# Sheet1.net
KiCad netlist of a schematic drawn in Altium Designer
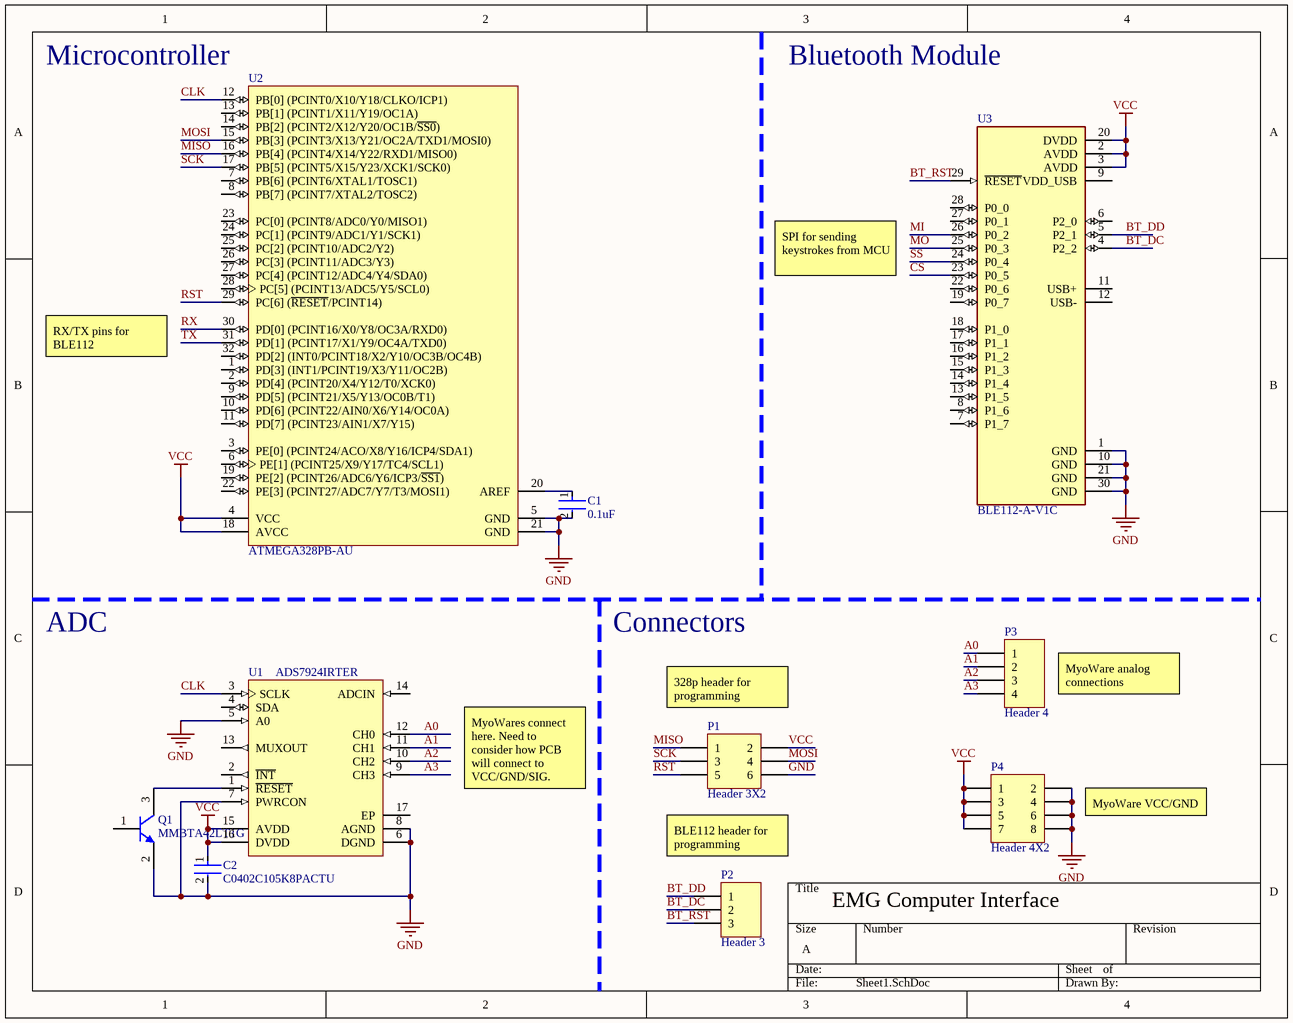
[diagram p0: Sheet1.SchDoc]

(export (version "E")
  (design (tool "Eeschema 10.0.6"))
  (components
    (comp (ref "C1")
      (value "0.1uF")
      (footprint "FP-GRM033-0_03-IPC_C")
      (description "Chip Multilayer Ceramic Capacitors for General Purpose, 0201, 0.10uF, X5R, 15%, 10%, 10V")
      (fields (field (name "TOLERANCE") "10%") (field (name "VOLTAGE") "10V"))
      (libsource (lib "Altium Content Vault") (part "b4654b650e69147ec39a6b967a45e02"))
    )
    (comp (ref "C2")
      (value "C0402C105K8PACTU")
      (footprint "FP-C0402C105K8PACTU-MFG")
      (description "CAP CER 1UF 10V X5R 0402")
      (fields (field (name "VOLTAGE") "10V") (field (name "TOLERANCE") "10%"))
      (libsource (lib "Altium Content Vault") (part "11868f565c42a9108669ba33697ecf6"))
    )
    (comp (ref "P1")
      (value "Header 3X2")
      (footprint "HDR2X3")
      (description "Header, 3-Pin, Dual row")
      (fields (field (name "PUBLISHER") "Altium Limited"))
      (libsource (lib "Miscellaneous Connectors") (part "Header 3X2"))
    )
    (comp (ref "P2")
      (value "Header 3")
      (footprint "HDR1X3")
      (description "Header, 3-Pin")
      (fields (field (name "PUBLISHER") "Altium Limited"))
      (libsource (lib "Miscellaneous Connectors") (part "Header 3"))
    )
    (comp (ref "P3")
      (value "Header 4")
      (footprint "HDR1X4")
      (description "Header, 4-Pin")
      (fields (field (name "PUBLISHER") "Altium Limited"))
      (libsource (lib "Miscellaneous Connectors") (part "Header 4"))
    )
    (comp (ref "P4")
      (value "Header 4X2")
      (footprint "HDR2X4")
      (description "Header, 4-Pin, Dual row")
      (fields (field (name "PUBLISHER") "Altium Limited"))
      (libsource (lib "Miscellaneous Connectors") (part "Header 4X2"))
    )
    (comp (ref "Q1")
      (value "MMBTA42LT1G")
      (footprint "ONSC-SOT-23-3-318-08_V")
      (description "High Voltage Transistor, NPN Silicon, 3-Pin SOT-23, Pb-Free, Tape and Reel")
      (fields (field (name "MANUFACTURER") "On Semiconductor"))
      (libsource (lib "Altium Content Vault") (part "ONSC-NPN-B1E2C3-3"))
    )
    (comp (ref "U1")
      (value "ADS7924IRTER")
      (footprint "TI-RTE16-1700X1700TP_V")
      (fields (field (name "MANUFACTURER") "Texas Instruments"))
      (libsource (lib "Altium Content Vault") (part "TI-ADS7924RTE16-1700X1700TP"))
    )
    (comp (ref "U2")
      (value "ATMEGA328PB-AU")
      (footprint "ATML-32A_L")
      (fields (field (name "MANUFACTURER") "Microchip"))
      (libsource (lib "Altium Content Vault") (part "ATML-ATMEGA328PB-32A"))
    )
    (comp (ref "U3")
      (value "BLE112-A-V1C")
      (footprint "BLUEGIGA_BLE112-A")
      (description "Low Energy Bluetooth Module")
      (libsource (lib "BLE112-A-V1C") (part "BLE112-A-V1C"))
    )
  )
  (nets
    (net (code "1") (name "/A0") (class "Default")
      (node (ref "P3") (pin "1") (pinfunction "1_1") (pintype "passive"))
      (node (ref "U1") (pin "12") (pinfunction "CH0_12") (pintype "input"))
    )
    (net (code "2") (name "/A1") (class "Default")
      (node (ref "P3") (pin "2") (pinfunction "2_2") (pintype "passive"))
      (node (ref "U1") (pin "11") (pinfunction "CH1_11") (pintype "input"))
    )
    (net (code "3") (name "/A2") (class "Default")
      (node (ref "P3") (pin "3") (pinfunction "3_3") (pintype "passive"))
      (node (ref "U1") (pin "10") (pinfunction "CH2_10") (pintype "input"))
    )
    (net (code "4") (name "/A3") (class "Default")
      (node (ref "P3") (pin "4") (pinfunction "4_4") (pintype "passive"))
      (node (ref "U1") (pin "9") (pinfunction "CH3_9") (pintype "input"))
    )
    (net (code "5") (name "/BT_DC") (class "Default")
      (node (ref "P2") (pin "2") (pinfunction "2_2") (pintype "passive"))
      (node (ref "U3") (pin "4") (pinfunction "P2_2_4") (pintype "bidirectional"))
    )
    (net (code "6") (name "/BT_DD") (class "Default")
      (node (ref "P2") (pin "1") (pinfunction "1_1") (pintype "passive"))
      (node (ref "U3") (pin "5") (pinfunction "P2_1_5") (pintype "bidirectional"))
    )
    (net (code "7") (name "/BT_RST") (class "Default")
      (node (ref "P2") (pin "3") (pinfunction "3_3") (pintype "passive"))
      (node (ref "U3") (pin "29") (pinfunction "~{RESET}_29") (pintype "input"))
    )
    (net (code "8") (name "/CLK") (class "Default")
      (node (ref "U1") (pin "3") (pinfunction "SCLK_3") (pintype "input"))
      (node (ref "U2") (pin "12") (pinfunction "PB[0]_(PCINT0/X10/Y18/CLKO/ICP1)_12") (pintype "bidirectional"))
    )
    (net (code "9") (name "/CS") (class "Default")
      (node (ref "U3") (pin "23") (pinfunction "P0_5_23") (pintype "bidirectional"))
    )
    (net (code "10") (name "/MI") (class "Default")
      (node (ref "U3") (pin "26") (pinfunction "P0_2_26") (pintype "bidirectional"))
    )
    (net (code "11") (name "/MISO") (class "Default")
      (node (ref "P1") (pin "1") (pinfunction "1_1") (pintype "passive"))
      (node (ref "U2") (pin "16") (pinfunction "PB[4]_(PCINT4/X14/Y22/RXD1/MISO0)_16") (pintype "bidirectional"))
    )
    (net (code "12") (name "/MO") (class "Default")
      (node (ref "U3") (pin "25") (pinfunction "P0_3_25") (pintype "bidirectional"))
    )
    (net (code "13") (name "/MOSI") (class "Default")
      (node (ref "P1") (pin "4") (pinfunction "4_4") (pintype "passive"))
      (node (ref "U2") (pin "15") (pinfunction "PB[3]_(PCINT3/X13/Y21/OC2A/TXD1/MOSI0)_15") (pintype "bidirectional"))
    )
    (net (code "14") (name "/RST") (class "Default")
      (node (ref "P1") (pin "5") (pinfunction "5_5") (pintype "passive"))
      (node (ref "U2") (pin "29") (pinfunction "PC[6]_(~{RESET}/PCINT14)_29") (pintype "bidirectional"))
    )
    (net (code "15") (name "/RX") (class "Default")
      (node (ref "U2") (pin "30") (pinfunction "PD[0]_(PCINT16/X0/Y8/OC3A/RXD0)_30") (pintype "bidirectional"))
    )
    (net (code "16") (name "/SCK") (class "Default")
      (node (ref "P1") (pin "3") (pinfunction "3_3") (pintype "passive"))
      (node (ref "U2") (pin "17") (pinfunction "PB[5]_(PCINT5/X15/Y23/XCK1/SCK0)_17") (pintype "bidirectional"))
    )
    (net (code "17") (name "/SS") (class "Default")
      (node (ref "U3") (pin "24") (pinfunction "P0_4_24") (pintype "bidirectional"))
    )
    (net (code "18") (name "/TX") (class "Default")
      (node (ref "U2") (pin "31") (pinfunction "PD[1]_(PCINT17/X1/Y9/OC4A/TXD0)_31") (pintype "bidirectional"))
    )
    (net (code "19") (name "GND") (class "Default")
      (node (ref "C1") (pin "2") (pinfunction "2_2") (pintype "passive"))
      (node (ref "C2") (pin "2") (pinfunction "2_2") (pintype "passive"))
      (node (ref "P1") (pin "6") (pinfunction "6_6") (pintype "passive"))
      (node (ref "P4") (pin "2") (pinfunction "2_2") (pintype "passive"))
      (node (ref "P4") (pin "4") (pinfunction "4_4") (pintype "passive"))
      (node (ref "P4") (pin "6") (pinfunction "6_6") (pintype "passive"))
      (node (ref "P4") (pin "8") (pinfunction "8_8") (pintype "passive"))
      (node (ref "Q1") (pin "2") (pinfunction "E_2") (pintype "passive"))
      (node (ref "U1") (pin "5") (pinfunction "A0_5") (pintype "input"))
      (node (ref "U1") (pin "6") (pinfunction "DGND_6") (pintype "power_in"))
      (node (ref "U1") (pin "7") (pinfunction "PWRCON_7") (pintype "input"))
      (node (ref "U1") (pin "8") (pinfunction "AGND_8") (pintype "power_in"))
      (node (ref "U2") (pin "21") (pinfunction "GND_21") (pintype "power_in"))
      (node (ref "U2") (pin "5") (pinfunction "GND_5") (pintype "power_in"))
      (node (ref "U3") (pin "1") (pinfunction "GND_1") (pintype "power_in"))
      (node (ref "U3") (pin "10") (pinfunction "GND_10") (pintype "power_in"))
      (node (ref "U3") (pin "21") (pinfunction "GND_21") (pintype "power_in"))
      (node (ref "U3") (pin "30") (pinfunction "GND_30") (pintype "power_in"))
    )
    (net (code "20") (name "Net-(Q1-C)") (class "Default")
      (node (ref "Q1") (pin "3") (pinfunction "C_3") (pintype "passive"))
      (node (ref "U1") (pin "1") (pinfunction "~{RESET}_1") (pintype "input"))
    )
    (net (code "21") (name "Net-(U2-AREF)") (class "Default")
      (node (ref "C1") (pin "1") (pinfunction "1_1") (pintype "passive"))
      (node (ref "U2") (pin "20") (pinfunction "AREF_20") (pintype "passive"))
    )
    (net (code "22") (name "VCC") (class "Default")
      (node (ref "C2") (pin "1") (pinfunction "1_1") (pintype "passive"))
      (node (ref "P1") (pin "2") (pinfunction "2_2") (pintype "passive"))
      (node (ref "P4") (pin "1") (pinfunction "1_1") (pintype "passive"))
      (node (ref "P4") (pin "3") (pinfunction "3_3") (pintype "passive"))
      (node (ref "P4") (pin "5") (pinfunction "5_5") (pintype "passive"))
      (node (ref "P4") (pin "7") (pinfunction "7_7") (pintype "passive"))
      (node (ref "U1") (pin "15") (pinfunction "AVDD_15") (pintype "power_in"))
      (node (ref "U1") (pin "16") (pinfunction "DVDD_16") (pintype "power_in"))
      (node (ref "U2") (pin "18") (pinfunction "AVCC_18") (pintype "power_in"))
      (node (ref "U2") (pin "4") (pinfunction "VCC_4") (pintype "power_in"))
      (node (ref "U3") (pin "2") (pinfunction "AVDD_2") (pintype "power_in"))
      (node (ref "U3") (pin "20") (pinfunction "DVDD_20") (pintype "power_in"))
      (node (ref "U3") (pin "3") (pinfunction "AVDD_3") (pintype "power_in"))
    )
    (net (code "23") (name "unconnected-(Q1-B-Pad1)") (class "Default")
      (node (ref "Q1") (pin "1") (pinfunction "B_1") (pintype "passive"))
    )
    (net (code "24") (name "unconnected-(U1-ADCIN-Pad14)") (class "Default")
      (node (ref "U1") (pin "14") (pinfunction "ADCIN_14") (pintype "input"))
    )
    (net (code "25") (name "unconnected-(U1-EP-Pad17)") (class "Default")
      (node (ref "U1") (pin "17") (pinfunction "EP_17") (pintype "power_in"))
    )
    (net (code "26") (name "unconnected-(U1-MUXOUT-Pad13)") (class "Default")
      (node (ref "U1") (pin "13") (pinfunction "MUXOUT_13") (pintype "output"))
    )
    (net (code "27") (name "unconnected-(U1-SDA-Pad4)") (class "Default")
      (node (ref "U1") (pin "4") (pinfunction "SDA_4") (pintype "bidirectional"))
    )
    (net (code "28") (name "unconnected-(U1-~{INT}-Pad2)") (class "Default")
      (node (ref "U1") (pin "2") (pinfunction "~{INT}_2") (pintype "output"))
    )
    (net (code "29") (name "unconnected-(U2-PB[1]_(PCINT1{slash}X11{slash}Y19{slash}OC1A)-Pad13)") (class "Default")
      (node (ref "U2") (pin "13") (pinfunction "PB[1]_(PCINT1/X11/Y19/OC1A)_13") (pintype "bidirectional"))
    )
    (net (code "30") (name "unconnected-(U2-PB[2]_(PCINT2{slash}X12{slash}Y20{slash}OC1B{slash}~{SS0})-Pad14)") (class "Default")
      (node (ref "U2") (pin "14") (pinfunction "PB[2]_(PCINT2/X12/Y20/OC1B/~{SS0})_14") (pintype "bidirectional"))
    )
    (net (code "31") (name "unconnected-(U2-PB[6]_(PCINT6{slash}XTAL1{slash}TOSC1)-Pad7)") (class "Default")
      (node (ref "U2") (pin "7") (pinfunction "PB[6]_(PCINT6/XTAL1/TOSC1)_7") (pintype "bidirectional"))
    )
    (net (code "32") (name "unconnected-(U2-PB[7]_(PCINT7{slash}XTAL2{slash}TOSC2)-Pad8)") (class "Default")
      (node (ref "U2") (pin "8") (pinfunction "PB[7]_(PCINT7/XTAL2/TOSC2)_8") (pintype "bidirectional"))
    )
    (net (code "33") (name "unconnected-(U2-PC[0]_(PCINT8{slash}ADC0{slash}Y0{slash}MISO1)-Pad23)") (class "Default")
      (node (ref "U2") (pin "23") (pinfunction "PC[0]_(PCINT8/ADC0/Y0/MISO1)_23") (pintype "bidirectional"))
    )
    (net (code "34") (name "unconnected-(U2-PC[1]_(PCINT9{slash}ADC1{slash}Y1{slash}SCK1)-Pad24)") (class "Default")
      (node (ref "U2") (pin "24") (pinfunction "PC[1]_(PCINT9/ADC1/Y1/SCK1)_24") (pintype "bidirectional"))
    )
    (net (code "35") (name "unconnected-(U2-PC[2]_(PCINT10{slash}ADC2{slash}Y2)-Pad25)") (class "Default")
      (node (ref "U2") (pin "25") (pinfunction "PC[2]_(PCINT10/ADC2/Y2)_25") (pintype "bidirectional"))
    )
    (net (code "36") (name "unconnected-(U2-PC[3]_(PCINT11{slash}ADC3{slash}Y3)-Pad26)") (class "Default")
      (node (ref "U2") (pin "26") (pinfunction "PC[3]_(PCINT11/ADC3/Y3)_26") (pintype "bidirectional"))
    )
    (net (code "37") (name "unconnected-(U2-PC[4]_(PCINT12{slash}ADC4{slash}Y4{slash}SDA0)-Pad27)") (class "Default")
      (node (ref "U2") (pin "27") (pinfunction "PC[4]_(PCINT12/ADC4/Y4/SDA0)_27") (pintype "bidirectional"))
    )
    (net (code "38") (name "unconnected-(U2-PC[5]_(PCINT13{slash}ADC5{slash}Y5{slash}SCL0)-Pad28)") (class "Default")
      (node (ref "U2") (pin "28") (pinfunction "PC[5]_(PCINT13/ADC5/Y5/SCL0)_28") (pintype "bidirectional"))
    )
    (net (code "39") (name "unconnected-(U2-PD[2]_(INT0{slash}PCINT18{slash}X2{slash}Y10{slash}OC3B{slash}OC4B)-Pad32)") (class "Default")
      (node (ref "U2") (pin "32") (pinfunction "PD[2]_(INT0/PCINT18/X2/Y10/OC3B/OC4B)_32") (pintype "bidirectional"))
    )
    (net (code "40") (name "unconnected-(U2-PD[3]_(INT1{slash}PCINT19{slash}X3{slash}Y11{slash}OC2B)-Pad1)") (class "Default")
      (node (ref "U2") (pin "1") (pinfunction "PD[3]_(INT1/PCINT19/X3/Y11/OC2B)_1") (pintype "bidirectional"))
    )
    (net (code "41") (name "unconnected-(U2-PD[4]_(PCINT20{slash}X4{slash}Y12{slash}T0{slash}XCK0)-Pad2)") (class "Default")
      (node (ref "U2") (pin "2") (pinfunction "PD[4]_(PCINT20/X4/Y12/T0/XCK0)_2") (pintype "bidirectional"))
    )
    (net (code "42") (name "unconnected-(U2-PD[5]_(PCINT21{slash}X5{slash}Y13{slash}OC0B{slash}T1)-Pad9)") (class "Default")
      (node (ref "U2") (pin "9") (pinfunction "PD[5]_(PCINT21/X5/Y13/OC0B/T1)_9") (pintype "bidirectional"))
    )
    (net (code "43") (name "unconnected-(U2-PD[6]_(PCINT22{slash}AIN0{slash}X6{slash}Y14{slash}OC0A)-Pad10)") (class "Default")
      (node (ref "U2") (pin "10") (pinfunction "PD[6]_(PCINT22/AIN0/X6/Y14/OC0A)_10") (pintype "bidirectional"))
    )
    (net (code "44") (name "unconnected-(U2-PD[7]_(PCINT23{slash}AIN1{slash}X7{slash}Y15)-Pad11)") (class "Default")
      (node (ref "U2") (pin "11") (pinfunction "PD[7]_(PCINT23/AIN1/X7/Y15)_11") (pintype "bidirectional"))
    )
    (net (code "45") (name "unconnected-(U2-PE[0]_(PCINT24{slash}ACO{slash}X8{slash}Y16{slash}ICP4{slash}SDA1)-Pad3)") (class "Default")
      (node (ref "U2") (pin "3") (pinfunction "PE[0]_(PCINT24/ACO/X8/Y16/ICP4/SDA1)_3") (pintype "bidirectional"))
    )
    (net (code "46") (name "unconnected-(U2-PE[1]_(PCINT25{slash}X9{slash}Y17{slash}TC4{slash}SCL1)-Pad6)") (class "Default")
      (node (ref "U2") (pin "6") (pinfunction "PE[1]_(PCINT25/X9/Y17/TC4/SCL1)_6") (pintype "bidirectional"))
    )
    (net (code "47") (name "unconnected-(U2-PE[2]_(PCINT26{slash}ADC6{slash}Y6{slash}ICP3{slash}~{SS1})-Pad19)") (class "Default")
      (node (ref "U2") (pin "19") (pinfunction "PE[2]_(PCINT26/ADC6/Y6/ICP3/~{SS1})_19") (pintype "bidirectional"))
    )
    (net (code "48") (name "unconnected-(U2-PE[3]_(PCINT27{slash}ADC7{slash}Y7{slash}T3{slash}MOSI1)-Pad22)") (class "Default")
      (node (ref "U2") (pin "22") (pinfunction "PE[3]_(PCINT27/ADC7/Y7/T3/MOSI1)_22") (pintype "bidirectional"))
    )
    (net (code "49") (name "unconnected-(U3-P0_0-Pad28)") (class "Default")
      (node (ref "U3") (pin "28") (pinfunction "P0_0_28") (pintype "bidirectional"))
    )
    (net (code "50") (name "unconnected-(U3-P0_1-Pad27)") (class "Default")
      (node (ref "U3") (pin "27") (pinfunction "P0_1_27") (pintype "bidirectional"))
    )
    (net (code "51") (name "unconnected-(U3-P0_6-Pad22)") (class "Default")
      (node (ref "U3") (pin "22") (pinfunction "P0_6_22") (pintype "bidirectional"))
    )
    (net (code "52") (name "unconnected-(U3-P0_7-Pad19)") (class "Default")
      (node (ref "U3") (pin "19") (pinfunction "P0_7_19") (pintype "bidirectional"))
    )
    (net (code "53") (name "unconnected-(U3-P1_0-Pad18)") (class "Default")
      (node (ref "U3") (pin "18") (pinfunction "P1_0_18") (pintype "bidirectional"))
    )
    (net (code "54") (name "unconnected-(U3-P1_1-Pad17)") (class "Default")
      (node (ref "U3") (pin "17") (pinfunction "P1_1_17") (pintype "bidirectional"))
    )
    (net (code "55") (name "unconnected-(U3-P1_2-Pad16)") (class "Default")
      (node (ref "U3") (pin "16") (pinfunction "P1_2_16") (pintype "bidirectional"))
    )
    (net (code "56") (name "unconnected-(U3-P1_3-Pad15)") (class "Default")
      (node (ref "U3") (pin "15") (pinfunction "P1_3_15") (pintype "bidirectional"))
    )
    (net (code "57") (name "unconnected-(U3-P1_4-Pad14)") (class "Default")
      (node (ref "U3") (pin "14") (pinfunction "P1_4_14") (pintype "bidirectional"))
    )
    (net (code "58") (name "unconnected-(U3-P1_5-Pad13)") (class "Default")
      (node (ref "U3") (pin "13") (pinfunction "P1_5_13") (pintype "bidirectional"))
    )
    (net (code "59") (name "unconnected-(U3-P1_6-Pad8)") (class "Default")
      (node (ref "U3") (pin "8") (pinfunction "P1_6_8") (pintype "bidirectional"))
    )
    (net (code "60") (name "unconnected-(U3-P1_7-Pad7)") (class "Default")
      (node (ref "U3") (pin "7") (pinfunction "P1_7_7") (pintype "bidirectional"))
    )
    (net (code "61") (name "unconnected-(U3-P2_0-Pad6)") (class "Default")
      (node (ref "U3") (pin "6") (pinfunction "P2_0_6") (pintype "bidirectional"))
    )
    (net (code "62") (name "unconnected-(U3-USB+-Pad11)") (class "Default")
      (node (ref "U3") (pin "11") (pinfunction "USB+_11") (pintype "passive"))
    )
    (net (code "63") (name "unconnected-(U3-USB--Pad12)") (class "Default")
      (node (ref "U3") (pin "12") (pinfunction "USB-_12") (pintype "passive"))
    )
    (net (code "64") (name "unconnected-(U3-VDD_USB-Pad9)") (class "Default")
      (node (ref "U3") (pin "9") (pinfunction "VDD_USB_9") (pintype "power_in"))
    )
  )
)
